# DXP.net
KiCad netlist of a schematic drawn in Altium Designer
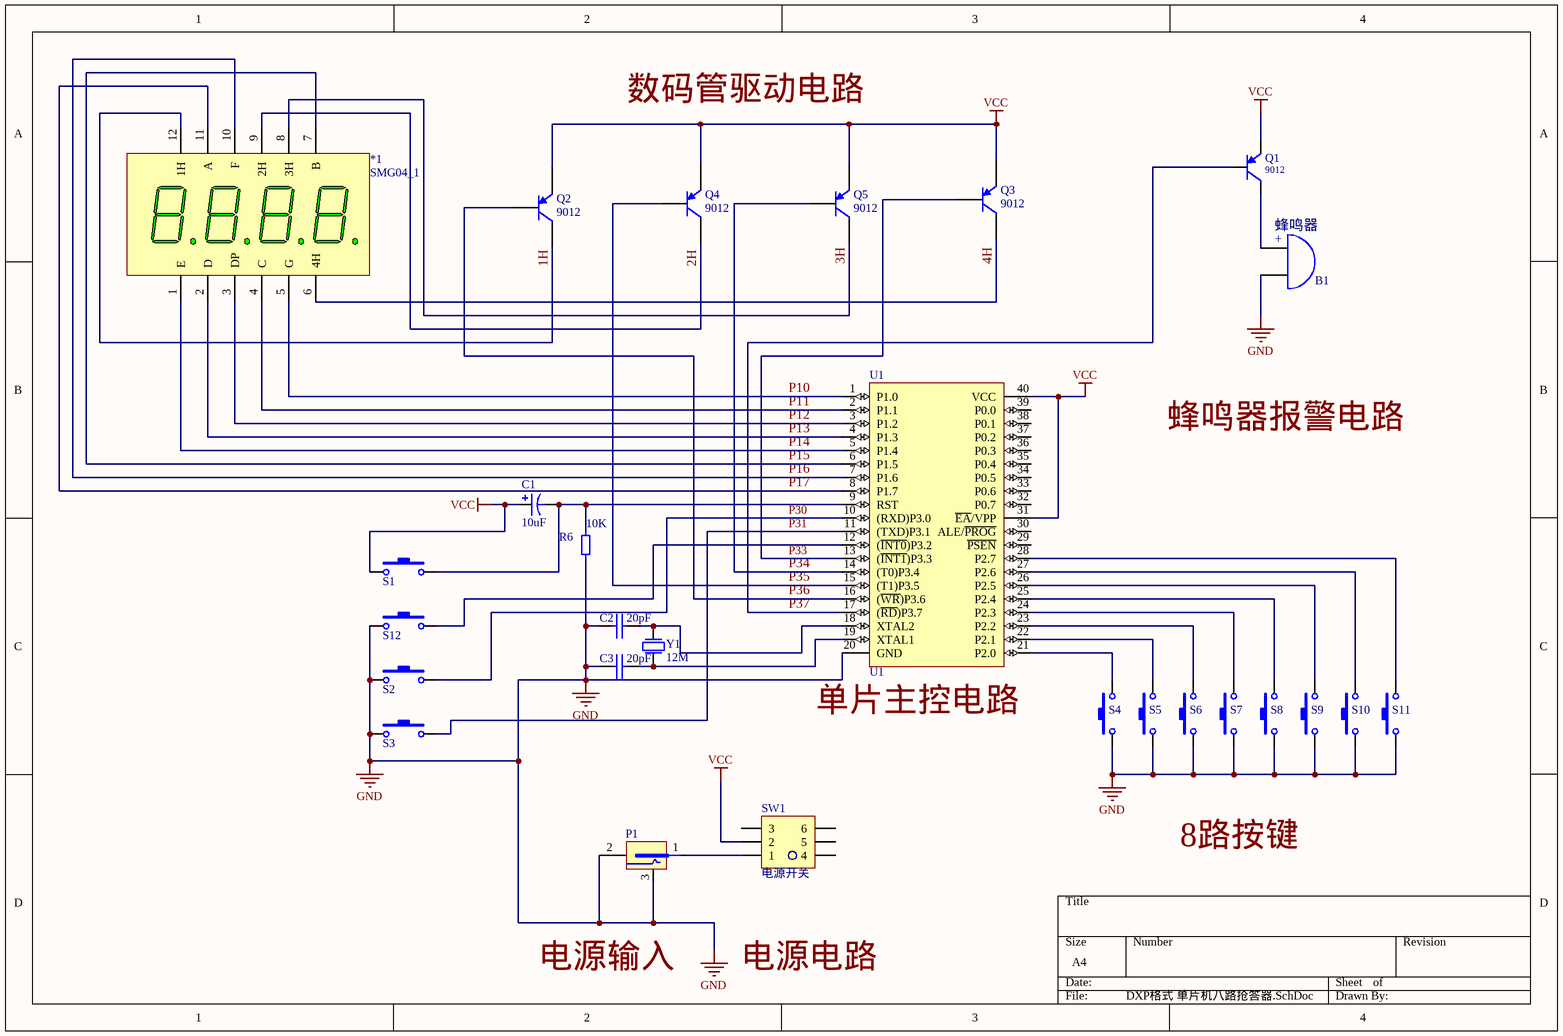
[diagram p0: DXP格式 单片机八路抢答器.SchDoc]

(export (version "E")
  (design (tool "Eeschema 10.0.6"))
  (components
    (comp (ref "*1") (value "SMG04_1") (footprint "SMG04") (libsource (lib "我自己的") (part "SMG04_1")))
    (comp (ref "B1")
      (value "蜂鸣器")
      (footprint "Bett")
      (description "Bell")
      (libsource (lib "实验板原理图") (part "BELL"))
    )
    (comp (ref "C1")
      (value "10uF")
      (footprint "C_10")
      (description "Polarized Capacitor (Radial)")
      (fields (field (name "PUBLISHER") "Altium Limited"))
      (libsource (lib "简易动环监控系统") (part "Cap Pol1"))
    )
    (comp (ref "C2")
      (value "20pF")
      (footprint "CAP5")
      (description "电容")
      (libsource (lib "C8051F020最小2") (part "CAP"))
    )
    (comp (ref "C3")
      (value "20pF")
      (footprint "CAP5")
      (description "电容")
      (libsource (lib "C8051F020最小2") (part "CAP"))
    )
    (comp (ref "P1") (value "电源输入") (footprint "DC2.1") (libsource (lib "我自己的") (part "POWER")))
    (comp (ref "Q1")
      (value "9012")
      (footprint "s三极管直插")
      (description "PNP General Purpose Amplifier")
      (fields (field (name "PUBLISHER") "Altium Limited"))
      (libsource (lib "实验板原理图") (part "2N3906"))
    )
    (comp (ref "Q2")
      (value "9012")
      (footprint "s三极管直插")
      (description "PNP General Purpose Amplifier")
      (fields (field (name "PUBLISHER") "Altium Limited"))
      (libsource (lib "Miscellaneous Devices") (part "2N3906"))
    )
    (comp (ref "Q3")
      (value "9012")
      (footprint "s三极管直插")
      (description "PNP General Purpose Amplifier")
      (fields (field (name "PUBLISHER") "Altium Limited"))
      (libsource (lib "Miscellaneous Devices") (part "2N3906"))
    )
    (comp (ref "Q4")
      (value "9012")
      (footprint "s三极管直插")
      (description "PNP General Purpose Amplifier")
      (fields (field (name "PUBLISHER") "Altium Limited"))
      (libsource (lib "Miscellaneous Devices") (part "2N3906"))
    )
    (comp (ref "Q5")
      (value "9012")
      (footprint "s三极管直插")
      (description "PNP General Purpose Amplifier")
      (fields (field (name "PUBLISHER") "Altium Limited"))
      (libsource (lib "Miscellaneous Devices") (part "2N3906"))
    )
    (comp (ref "R6") (value "10K") (footprint "AXIAL0.3") (libsource (lib "C8051F020最小2") (part "RES2")))
    (comp (ref "S1")
      (value "SW-PB")
      (footprint "key")
      (description "Switch")
      (fields (field (name "PUBLISHER") "Altium Limited"))
      (libsource (lib "实验板原理图") (part "SW-PB"))
    )
    (comp (ref "S2")
      (value "SW-PB")
      (footprint "key")
      (description "Switch")
      (fields (field (name "PUBLISHER") "Altium Limited"))
      (libsource (lib "实验板原理图") (part "SW-PB"))
    )
    (comp (ref "S3")
      (value "SW-PB")
      (footprint "key")
      (description "Switch")
      (fields (field (name "PUBLISHER") "Altium Limited"))
      (libsource (lib "实验板原理图") (part "SW-PB"))
    )
    (comp (ref "S4")
      (value "SW-PB")
      (footprint "key")
      (description "Switch")
      (fields (field (name "PUBLISHER") "Altium Limited"))
      (libsource (lib "实验板原理图") (part "SW-PB"))
    )
    (comp (ref "S5")
      (value "SW-PB")
      (footprint "key")
      (description "Switch")
      (fields (field (name "PUBLISHER") "Altium Limited"))
      (libsource (lib "实验板原理图") (part "SW-PB"))
    )
    (comp (ref "S6")
      (value "SW-PB")
      (footprint "key")
      (description "Switch")
      (fields (field (name "PUBLISHER") "Altium Limited"))
      (libsource (lib "实验板原理图") (part "SW-PB"))
    )
    (comp (ref "S7")
      (value "SW-PB")
      (footprint "key")
      (description "Switch")
      (fields (field (name "PUBLISHER") "Altium Limited"))
      (libsource (lib "实验板原理图") (part "SW-PB"))
    )
    (comp (ref "S8")
      (value "SW-PB")
      (footprint "key")
      (description "Switch")
      (fields (field (name "PUBLISHER") "Altium Limited"))
      (libsource (lib "实验板原理图") (part "SW-PB"))
    )
    (comp (ref "S9")
      (value "SW-PB")
      (footprint "key")
      (description "Switch")
      (fields (field (name "PUBLISHER") "Altium Limited"))
      (libsource (lib "实验板原理图") (part "SW-PB"))
    )
    (comp (ref "S10")
      (value "SW-PB")
      (footprint "key")
      (description "Switch")
      (fields (field (name "PUBLISHER") "Altium Limited"))
      (libsource (lib "实验板原理图") (part "SW-PB"))
    )
    (comp (ref "S11")
      (value "SW-PB")
      (footprint "key")
      (description "Switch")
      (fields (field (name "PUBLISHER") "Altium Limited"))
      (libsource (lib "实验板原理图") (part "SW-PB"))
    )
    (comp (ref "S12")
      (value "SW-PB")
      (footprint "key")
      (description "Switch")
      (fields (field (name "PUBLISHER") "Altium Limited"))
      (libsource (lib "实验板原理图") (part "SW-PB"))
    )
    (comp (ref "SW1") (value "电源开关") (footprint "sw_自锁 1") (libsource (lib "我自己的") (part "SW1")))
    (comp (ref "U1") (value "U1") (footprint "DIP40 - 做板") (libsource (lib "实验板原理图") (part "U1")))
    (comp (ref "Y1")
      (value "12M")
      (footprint "XTAL")
      (description "Crystal Oscillator")
      (libsource (lib "C8051F020最小2") (part "16M"))
    )
  )
  (nets
    (net (code "1") (name "/1H") (class "Default")
      (node (ref "*1") (pin "12") (pinfunction "1H_12") (pintype "passive"))
      (node (ref "Q2") (pin "3") (pinfunction "C_3") (pintype "passive"))
    )
    (net (code "2") (name "/2H") (class "Default")
      (node (ref "*1") (pin "9") (pinfunction "2H_9") (pintype "passive"))
      (node (ref "Q4") (pin "3") (pinfunction "C_3") (pintype "passive"))
    )
    (net (code "3") (name "/3H") (class "Default")
      (node (ref "*1") (pin "8") (pinfunction "3H_8") (pintype "passive"))
      (node (ref "Q5") (pin "3") (pinfunction "C_3") (pintype "passive"))
    )
    (net (code "4") (name "/4H") (class "Default")
      (node (ref "*1") (pin "6") (pinfunction "4H_6") (pintype "passive"))
      (node (ref "Q3") (pin "3") (pinfunction "C_3") (pintype "passive"))
    )
    (net (code "6") (name "/P10") (class "Default")
      (node (ref "*1") (pin "5") (pinfunction "G_5") (pintype "passive"))
      (node (ref "U1") (pin "1") (pinfunction "P1.0_1") (pintype "bidirectional"))
    )
    (net (code "7") (name "/P11") (class "Default")
      (node (ref "*1") (pin "4") (pinfunction "C_4") (pintype "passive"))
      (node (ref "U1") (pin "2") (pinfunction "P1.1_2") (pintype "bidirectional"))
    )
    (net (code "8") (name "/P12") (class "Default")
      (node (ref "*1") (pin "3") (pinfunction "DP_3") (pintype "passive"))
      (node (ref "U1") (pin "3") (pinfunction "P1.2_3") (pintype "bidirectional"))
    )
    (net (code "9") (name "/P13") (class "Default")
      (node (ref "*1") (pin "2") (pinfunction "D_2") (pintype "passive"))
      (node (ref "U1") (pin "4") (pinfunction "P1.3_4") (pintype "bidirectional"))
    )
    (net (code "10") (name "/P14") (class "Default")
      (node (ref "*1") (pin "1") (pinfunction "E_1") (pintype "passive"))
      (node (ref "U1") (pin "5") (pinfunction "P1.4_5") (pintype "bidirectional"))
    )
    (net (code "11") (name "/P15") (class "Default")
      (node (ref "*1") (pin "7") (pinfunction "B_7") (pintype "passive"))
      (node (ref "U1") (pin "6") (pinfunction "P1.5_6") (pintype "bidirectional"))
    )
    (net (code "12") (name "/P16") (class "Default")
      (node (ref "*1") (pin "10") (pinfunction "F_10") (pintype "passive"))
      (node (ref "U1") (pin "7") (pinfunction "P1.6_7") (pintype "bidirectional"))
    )
    (net (code "13") (name "/P17") (class "Default")
      (node (ref "*1") (pin "11") (pinfunction "A_11") (pintype "passive"))
      (node (ref "U1") (pin "8") (pinfunction "P1.7_8") (pintype "bidirectional"))
    )
    (net (code "14") (name "/P30") (class "Default")
      (node (ref "S2") (pin "2") (pinfunction "2_2") (pintype "passive"))
      (node (ref "U1") (pin "10") (pinfunction "(RXD)P3.0_10") (pintype "bidirectional"))
    )
    (net (code "15") (name "/P31") (class "Default")
      (node (ref "S3") (pin "2") (pinfunction "2_2") (pintype "passive"))
      (node (ref "U1") (pin "11") (pinfunction "(TXD)P3.1_11") (pintype "bidirectional"))
    )
    (net (code "16") (name "/P33") (class "Default")
      (node (ref "Q3") (pin "2") (pinfunction "B_2") (pintype "passive"))
      (node (ref "U1") (pin "13") (pinfunction "(~{INT1})P3.3_13") (pintype "bidirectional"))
    )
    (net (code "17") (name "/P34") (class "Default")
      (node (ref "Q5") (pin "2") (pinfunction "B_2") (pintype "passive"))
      (node (ref "U1") (pin "14") (pinfunction "(T0)P3.4_14") (pintype "bidirectional"))
    )
    (net (code "18") (name "/P35") (class "Default")
      (node (ref "Q4") (pin "2") (pinfunction "B_2") (pintype "passive"))
      (node (ref "U1") (pin "15") (pinfunction "(T1)P3.5_15") (pintype "bidirectional"))
    )
    (net (code "19") (name "/P36") (class "Default")
      (node (ref "Q2") (pin "2") (pinfunction "B_2") (pintype "passive"))
      (node (ref "U1") (pin "16") (pinfunction "(~{WR})P3.6_16") (pintype "bidirectional"))
    )
    (net (code "20") (name "/P37") (class "Default")
      (node (ref "Q1") (pin "2") (pinfunction "B_2") (pintype "passive"))
      (node (ref "U1") (pin "17") (pinfunction "(~{RD})P3.7_17") (pintype "bidirectional"))
    )
    (net (code "26") (name "GND") (class "Default")
      (node (ref "B1") (pin "2") (pinfunction "B_2") (pintype "passive"))
      (node (ref "C2") (pin "1") (pinfunction "1_1") (pintype "passive"))
      (node (ref "C3") (pin "1") (pinfunction "1_1") (pintype "passive"))
      (node (ref "P1") (pin "2") (pintype "passive"))
      (node (ref "P1") (pin "3") (pintype "passive"))
      (node (ref "R6") (pin "1") (pinfunction "1_1") (pintype "passive"))
      (node (ref "S10") (pin "1") (pinfunction "1_1") (pintype "passive"))
      (node (ref "S11") (pin "1") (pinfunction "1_1") (pintype "passive"))
      (node (ref "S12") (pin "1") (pinfunction "1_1") (pintype "passive"))
      (node (ref "S2") (pin "1") (pinfunction "1_1") (pintype "passive"))
      (node (ref "S3") (pin "1") (pinfunction "1_1") (pintype "passive"))
      (node (ref "S4") (pin "1") (pinfunction "1_1") (pintype "passive"))
      (node (ref "S5") (pin "1") (pinfunction "1_1") (pintype "passive"))
      (node (ref "S6") (pin "1") (pinfunction "1_1") (pintype "passive"))
      (node (ref "S7") (pin "1") (pinfunction "1_1") (pintype "passive"))
      (node (ref "S8") (pin "1") (pinfunction "1_1") (pintype "passive"))
      (node (ref "S9") (pin "1") (pinfunction "1_1") (pintype "passive"))
      (node (ref "U1") (pin "20") (pinfunction "GND_20") (pintype "power_in"))
    )
    (net (code "27") (name "Net-(B1-A)") (class "Default")
      (node (ref "B1") (pin "1") (pinfunction "A_1") (pintype "passive"))
      (node (ref "Q1") (pin "3") (pinfunction "C_3") (pintype "passive"))
    )
    (net (code "28") (name "Net-(P1-Pad1)") (class "Default")
      (node (ref "P1") (pin "1") (pintype "passive"))
      (node (ref "SW1") (pin "1") (pinfunction "1_1") (pintype "passive"))
    )
    (net (code "29") (name "Net-(U1-(~{INT0})P3.2)") (class "Default")
      (node (ref "S12") (pin "2") (pinfunction "2_2") (pintype "passive"))
      (node (ref "U1") (pin "12") (pinfunction "(~{INT0})P3.2_12") (pintype "bidirectional"))
    )
    (net (code "30") (name "Net-(U1-P2.0)") (class "Default")
      (node (ref "S4") (pin "2") (pinfunction "2_2") (pintype "passive"))
      (node (ref "U1") (pin "21") (pinfunction "P2.0_21") (pintype "bidirectional"))
    )
    (net (code "31") (name "Net-(U1-P2.1)") (class "Default")
      (node (ref "S5") (pin "2") (pinfunction "2_2") (pintype "passive"))
      (node (ref "U1") (pin "22") (pinfunction "P2.1_22") (pintype "bidirectional"))
    )
    (net (code "32") (name "Net-(U1-P2.2)") (class "Default")
      (node (ref "S6") (pin "2") (pinfunction "2_2") (pintype "passive"))
      (node (ref "U1") (pin "23") (pinfunction "P2.2_23") (pintype "bidirectional"))
    )
    (net (code "33") (name "Net-(U1-P2.3)") (class "Default")
      (node (ref "S7") (pin "2") (pinfunction "2_2") (pintype "passive"))
      (node (ref "U1") (pin "24") (pinfunction "P2.3_24") (pintype "bidirectional"))
    )
    (net (code "34") (name "Net-(U1-P2.4)") (class "Default")
      (node (ref "S8") (pin "2") (pinfunction "2_2") (pintype "passive"))
      (node (ref "U1") (pin "25") (pinfunction "P2.4_25") (pintype "bidirectional"))
    )
    (net (code "35") (name "Net-(U1-P2.5)") (class "Default")
      (node (ref "S9") (pin "2") (pinfunction "2_2") (pintype "passive"))
      (node (ref "U1") (pin "26") (pinfunction "P2.5_26") (pintype "bidirectional"))
    )
    (net (code "36") (name "Net-(U1-P2.6)") (class "Default")
      (node (ref "S10") (pin "2") (pinfunction "2_2") (pintype "passive"))
      (node (ref "U1") (pin "27") (pinfunction "P2.6_27") (pintype "bidirectional"))
    )
    (net (code "37") (name "Net-(U1-P2.7)") (class "Default")
      (node (ref "S11") (pin "2") (pinfunction "2_2") (pintype "passive"))
      (node (ref "U1") (pin "28") (pinfunction "P2.7_28") (pintype "bidirectional"))
    )
    (net (code "38") (name "Net-(U1-RST)") (class "Default")
      (node (ref "C1") (pin "2") (pinfunction "2_2") (pintype "passive"))
      (node (ref "R6") (pin "2") (pinfunction "2_2") (pintype "passive"))
      (node (ref "S1") (pin "2") (pinfunction "2_2") (pintype "passive"))
      (node (ref "U1") (pin "9") (pinfunction "RST_9") (pintype "bidirectional"))
    )
    (net (code "39") (name "Net-(U1-XTAL1)") (class "Default")
      (node (ref "C3") (pin "2") (pinfunction "2_2") (pintype "passive"))
      (node (ref "U1") (pin "19") (pinfunction "XTAL1_19") (pintype "bidirectional"))
      (node (ref "Y1") (pin "2") (pinfunction "P2_2") (pintype "passive"))
    )
    (net (code "40") (name "Net-(U1-XTAL2)") (class "Default")
      (node (ref "C2") (pin "2") (pinfunction "2_2") (pintype "passive"))
      (node (ref "U1") (pin "18") (pinfunction "XTAL2_18") (pintype "bidirectional"))
      (node (ref "Y1") (pin "1") (pinfunction "P1_1") (pintype "passive"))
    )
    (net (code "41") (name "VCC") (class "Default")
      (node (ref "C1") (pin "1") (pinfunction "1_1") (pintype "passive"))
      (node (ref "Q1") (pin "1") (pinfunction "E_1") (pintype "passive"))
      (node (ref "Q2") (pin "1") (pinfunction "E_1") (pintype "passive"))
      (node (ref "Q3") (pin "1") (pinfunction "E_1") (pintype "passive"))
      (node (ref "Q4") (pin "1") (pinfunction "E_1") (pintype "passive"))
      (node (ref "Q5") (pin "1") (pinfunction "E_1") (pintype "passive"))
      (node (ref "S1") (pin "1") (pinfunction "1_1") (pintype "passive"))
      (node (ref "SW1") (pin "2") (pinfunction "2_2") (pintype "passive"))
      (node (ref "U1") (pin "31") (pinfunction "~{EA}/VPP_31") (pintype "power_in"))
      (node (ref "U1") (pin "40") (pinfunction "VCC_40") (pintype "power_in"))
    )
    (net (code "42") (name "unconnected-(SW1-Pad3)") (class "Default")
      (node (ref "SW1") (pin "3") (pinfunction "3_3") (pintype "passive"))
    )
    (net (code "43") (name "unconnected-(SW1-Pad4)") (class "Default")
      (node (ref "SW1") (pin "4") (pinfunction "4_4") (pintype "passive"))
    )
    (net (code "44") (name "unconnected-(SW1-Pad5)") (class "Default")
      (node (ref "SW1") (pin "5") (pinfunction "5_5") (pintype "passive"))
    )
    (net (code "45") (name "unconnected-(SW1-Pad6)") (class "Default")
      (node (ref "SW1") (pin "6") (pinfunction "6_6") (pintype "passive"))
    )
    (net (code "46") (name "unconnected-(U1-ALE{slash}~{PROG}-Pad30)") (class "Default")
      (node (ref "U1") (pin "30") (pinfunction "ALE/~{PROG}_30") (pintype "bidirectional"))
    )
    (net (code "47") (name "unconnected-(U1-P0.0-Pad39)") (class "Default")
      (node (ref "U1") (pin "39") (pinfunction "P0.0_39") (pintype "bidirectional"))
    )
    (net (code "48") (name "unconnected-(U1-P0.1-Pad38)") (class "Default")
      (node (ref "U1") (pin "38") (pinfunction "P0.1_38") (pintype "bidirectional"))
    )
    (net (code "49") (name "unconnected-(U1-P0.2-Pad37)") (class "Default")
      (node (ref "U1") (pin "37") (pinfunction "P0.2_37") (pintype "bidirectional"))
    )
    (net (code "50") (name "unconnected-(U1-P0.3-Pad36)") (class "Default")
      (node (ref "U1") (pin "36") (pinfunction "P0.3_36") (pintype "bidirectional"))
    )
    (net (code "51") (name "unconnected-(U1-P0.4-Pad35)") (class "Default")
      (node (ref "U1") (pin "35") (pinfunction "P0.4_35") (pintype "bidirectional"))
    )
    (net (code "52") (name "unconnected-(U1-P0.5-Pad34)") (class "Default")
      (node (ref "U1") (pin "34") (pinfunction "P0.5_34") (pintype "bidirectional"))
    )
    (net (code "53") (name "unconnected-(U1-P0.6-Pad33)") (class "Default")
      (node (ref "U1") (pin "33") (pinfunction "P0.6_33") (pintype "bidirectional"))
    )
    (net (code "54") (name "unconnected-(U1-P0.7-Pad32)") (class "Default")
      (node (ref "U1") (pin "32") (pinfunction "P0.7_32") (pintype "bidirectional"))
    )
    (net (code "55") (name "unconnected-(U1-~{PSEN}-Pad29)") (class "Default")
      (node (ref "U1") (pin "29") (pinfunction "~{PSEN}_29") (pintype "bidirectional"))
    )
  )
)
